# Power_Supply.net
KiCad netlist of a schematic drawn in Altium Designer
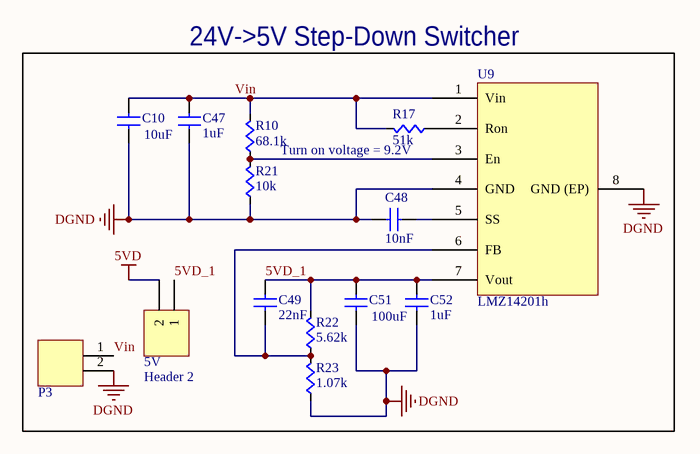
[diagram p0: Power_Supply.SchDoc]

(export (version "E")
  (design (tool "Eeschema 10.0.6"))
  (components
    (comp (ref "5V")
      (value "Header 2")
      (footprint "HDR1X2")
      (description "Header, 2-Pin")
      (fields (field (name "PUBLISHER") "Altium Limited"))
      (libsource (lib "Miscellaneous Connectors") (part "Header 2"))
    )
    (comp (ref "C10")
      (value "10uF")
      (footprint "CAP1210")
      (description "CAP CER 10UF 50V 20% X5R 1210")
      (fields (field (name "Comment") "CAP1210"))
      (libsource (lib "SubjuGator8") (part "CAP1210"))
    )
    (comp (ref "C47")
      (value "1uF")
      (footprint "CAP1206")
      (description "CAP CER 1UF 50V 10% X7R 1206")
      (fields (field (name "Comment") "Cap1206"))
      (libsource (lib "Passives") (part "Cap1206"))
    )
    (comp (ref "C48")
      (value "10nF")
      (footprint "CAPC0603")
      (fields (field (name "Comment") "Cap"))
      (libsource (lib "SubjuGator8") (part "Cap"))
    )
    (comp (ref "C49")
      (value "22nF")
      (footprint "CAPC0603")
      (fields (field (name "Comment") "Cap"))
      (libsource (lib "SubjuGator8") (part "Cap"))
    )
    (comp (ref "C51")
      (value "100uF")
      (footprint "CAP1210")
      (description "CAP CER 10UF 50V 20% X5R 1210")
      (fields (field (name "Comment") "CAP1210"))
      (libsource (lib "SubjuGator8") (part "CAP1210"))
    )
    (comp (ref "C52")
      (value "1uF")
      (footprint "CAP1206")
      (description "CAP CER 1UF 50V 10% X7R 1206")
      (fields (field (name "Comment") "Cap1206"))
      (libsource (lib "Passives") (part "Cap1206"))
    )
    (comp (ref "P3")
      (value "2-pin Horz Sherlock")
      (footprint "MOLEX-HDR-1X2-SHERLOCK-HORZ")
      (fields
        (field (name "MANUFACTURER PART NUMBER") "0353630260")
        (field (name "MANUFACTURER") "Molex Inc")
      )
      (libsource (lib "SubjuGator8") (part "MOLEX-HDR-1x2-SHERLOCK_RA"))
    )
    (comp (ref "R10")
      (value "68.1k")
      (footprint "RES0603")
      (fields (field (name "Comment") "Res"))
      (libsource (lib "SubjuGator8") (part "Res"))
    )
    (comp (ref "R17")
      (value "51k")
      (footprint "RES0603")
      (fields (field (name "Comment") "Res"))
      (libsource (lib "SubjuGator8") (part "Res"))
    )
    (comp (ref "R21")
      (value "10k")
      (footprint "RES0603")
      (fields (field (name "Comment") "Res"))
      (libsource (lib "SubjuGator8") (part "Res"))
    )
    (comp (ref "R22")
      (value "5.62k")
      (footprint "RES0603")
      (fields (field (name "Comment") "Res"))
      (libsource (lib "SubjuGator8") (part "Res"))
    )
    (comp (ref "R23")
      (value "1.07k")
      (footprint "RES0603")
      (fields (field (name "Comment") "Res"))
      (libsource (lib "SubjuGator8") (part "Res"))
    )
    (comp (ref "U9")
      (value "LMZ14201h")
      (footprint "TO-PMOD-7")
      (description "IC BUCK SYNC ADJ 1A TO-PMOD-7")
      (libsource (lib "ICs") (part "LMZ14201h"))
    )
  )
  (nets
    (net (code "1") (name "/5VD_1") (class "Default")
      (node (ref "5V") (pin "1") (pinfunction "1_1") (pintype "passive"))
      (node (ref "C49") (pin "2") (pinfunction "B_2") (pintype "passive"))
      (node (ref "C51") (pin "1") (pinfunction "A_1") (pintype "passive"))
      (node (ref "C52") (pin "1") (pinfunction "A_1") (pintype "passive"))
      (node (ref "R22") (pin "1") (pinfunction "A_1") (pintype "passive"))
      (node (ref "U9") (pin "7") (pinfunction "Vout_7") (pintype "passive"))
    )
    (net (code "2") (name "/Vin") (class "Default")
      (node (ref "C10") (pin "1") (pinfunction "A_1") (pintype "passive"))
      (node (ref "C47") (pin "1") (pinfunction "A_1") (pintype "passive"))
      (node (ref "P3") (pin "1") (pinfunction "1_1") (pintype "passive"))
      (node (ref "R10") (pin "1") (pinfunction "A_1") (pintype "passive"))
      (node (ref "R17") (pin "1") (pinfunction "A_1") (pintype "passive"))
      (node (ref "U9") (pin "1") (pinfunction "Vin_1") (pintype "passive"))
    )
    (net (code "3") (name "5VD") (class "Default")
      (node (ref "5V") (pin "2") (pinfunction "2_2") (pintype "passive"))
    )
    (net (code "4") (name "DGND") (class "Default")
      (node (ref "C10") (pin "2") (pinfunction "B_2") (pintype "passive"))
      (node (ref "C47") (pin "2") (pinfunction "B_2") (pintype "passive"))
      (node (ref "C48") (pin "1") (pinfunction "A_1") (pintype "passive"))
      (node (ref "C51") (pin "2") (pinfunction "B_2") (pintype "passive"))
      (node (ref "C52") (pin "2") (pinfunction "B_2") (pintype "passive"))
      (node (ref "P3") (pin "2") (pinfunction "2_2") (pintype "passive"))
      (node (ref "R21") (pin "2") (pinfunction "B_2") (pintype "passive"))
      (node (ref "R23") (pin "2") (pinfunction "B_2") (pintype "passive"))
      (node (ref "U9") (pin "4") (pinfunction "GND_4") (pintype "passive"))
      (node (ref "U9") (pin "8") (pinfunction "GND_(EP)_8") (pintype "passive"))
    )
    (net (code "5") (name "Net-(C48-B)") (class "Default")
      (node (ref "C48") (pin "2") (pinfunction "B_2") (pintype "passive"))
      (node (ref "U9") (pin "5") (pinfunction "SS_5") (pintype "passive"))
    )
    (net (code "6") (name "Net-(C49-A)") (class "Default")
      (node (ref "C49") (pin "1") (pinfunction "A_1") (pintype "passive"))
      (node (ref "R22") (pin "2") (pinfunction "B_2") (pintype "passive"))
      (node (ref "R23") (pin "1") (pinfunction "A_1") (pintype "passive"))
      (node (ref "U9") (pin "6") (pinfunction "FB_6") (pintype "passive"))
    )
    (net (code "7") (name "Net-(R10-B)") (class "Default")
      (node (ref "R10") (pin "2") (pinfunction "B_2") (pintype "passive"))
      (node (ref "R21") (pin "1") (pinfunction "A_1") (pintype "passive"))
      (node (ref "U9") (pin "3") (pinfunction "En_3") (pintype "passive"))
    )
    (net (code "8") (name "Net-(R17-B)") (class "Default")
      (node (ref "R17") (pin "2") (pinfunction "B_2") (pintype "passive"))
      (node (ref "U9") (pin "2") (pinfunction "Ron_2") (pintype "passive"))
    )
  )
)
